# Schematic.net
KiCad netlist of a schematic drawn in EAGLE
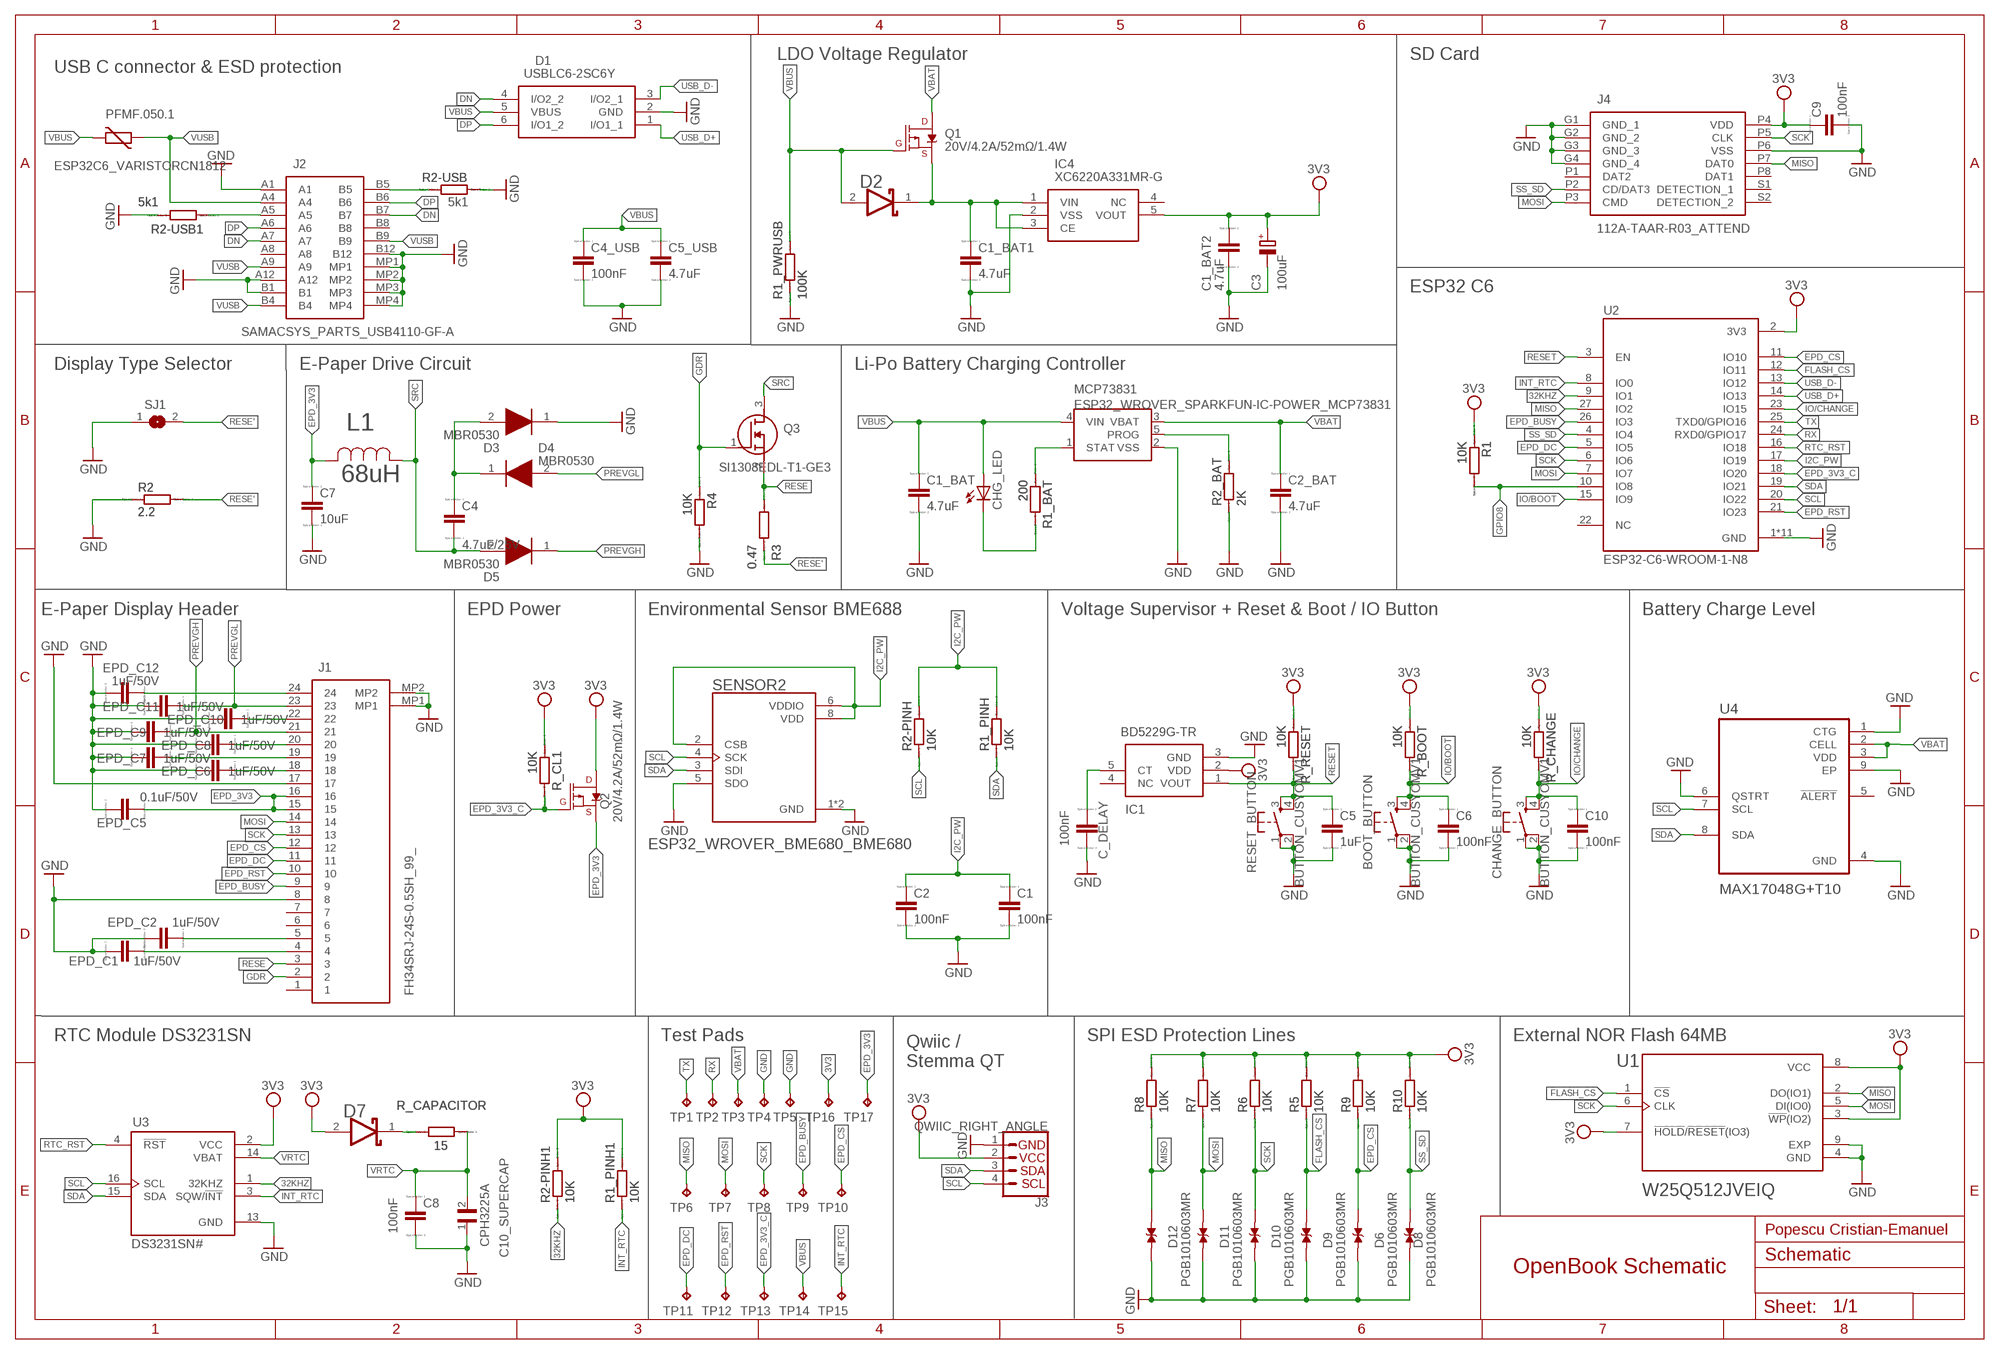
[diagram p0: schematic, sheet 1]

(export (version "E")
  (design (tool "Eeschema 10.0.6"))
  (components
    (comp (ref "BOOT_BUTTON")
      (value "BUTTON_CUSYOMV1")
      (footprint "eagle-import:MYBUTTON")
      (libsource (lib "eagle-import") (part "BUTTON_CUSYOMV1"))
    )
    (comp (ref "C1")
      (value "100nF")
      (footprint "eagle-import:ESP32_WROVER_EAGLE-LTSPICE_C0402")
      (libsource (lib "eagle-import") (part "ESP32_WROVER_EAGLE-LTSPICE_CC0402"))
    )
    (comp (ref "C1_BAT")
      (value "4.7uF")
      (footprint "eagle-import:ESP32_WROVER_EAGLE-LTSPICE_C0402")
      (libsource (lib "eagle-import") (part "ESP32_WROVER_EAGLE-LTSPICE_CC0402-4.7UF"))
    )
    (comp (ref "C1_BAT1")
      (value "4.7uF")
      (footprint "eagle-import:ESP32_WROVER_EAGLE-LTSPICE_C0402")
      (libsource (lib "eagle-import") (part "ESP32_WROVER_EAGLE-LTSPICE_CC0402-4.7UF"))
    )
    (comp (ref "C1_BAT2")
      (value "4.7uF")
      (footprint "eagle-import:ESP32_WROVER_EAGLE-LTSPICE_C0402")
      (libsource (lib "eagle-import") (part "ESP32_WROVER_EAGLE-LTSPICE_CC0402-4.7UF"))
    )
    (comp (ref "C2")
      (value "100nF")
      (footprint "eagle-import:ESP32_WROVER_EAGLE-LTSPICE_C0402")
      (libsource (lib "eagle-import") (part "ESP32_WROVER_EAGLE-LTSPICE_CC0402"))
    )
    (comp (ref "C2_BAT")
      (value "4.7uF")
      (footprint "eagle-import:ESP32_WROVER_EAGLE-LTSPICE_C0402")
      (libsource (lib "eagle-import") (part "ESP32_WROVER_EAGLE-LTSPICE_CC0402-4.7UF"))
    )
    (comp (ref "C3")
      (value "100uF")
      (footprint "eagle-import:RCL_CT3528")
      (libsource (lib "eagle-import") (part "RCL_CPOL-EUCT3528"))
    )
    (comp (ref "C4")
      (value "4.7uF/25V")
      (footprint "eagle-import:ESP32_WROVER_EAGLE-LTSPICE_C0402")
      (libsource (lib "eagle-import") (part "ESP32_WROVER_EAGLE-LTSPICE_CC0402-4.7UF"))
    )
    (comp (ref "C4_USB")
      (value "100nF")
      (footprint "eagle-import:ESP32_WROVER_EAGLE-LTSPICE_C0402")
      (libsource (lib "eagle-import") (part "ESP32_WROVER_EAGLE-LTSPICE_CC0402"))
    )
    (comp (ref "C5")
      (value "1uF")
      (footprint "eagle-import:ESP32_WROVER_EAGLE-LTSPICE_C0402")
      (libsource (lib "eagle-import") (part "ESP32_WROVER_EAGLE-LTSPICE_CC0402"))
    )
    (comp (ref "C5_USB")
      (value "4.7uF")
      (footprint "eagle-import:ESP32_WROVER_EAGLE-LTSPICE_C0402")
      (libsource (lib "eagle-import") (part "ESP32_WROVER_EAGLE-LTSPICE_CC0402-4.7UF"))
    )
    (comp (ref "C6")
      (value "100nF")
      (footprint "eagle-import:ESP32_WROVER_EAGLE-LTSPICE_C0402")
      (libsource (lib "eagle-import") (part "ESP32_WROVER_EAGLE-LTSPICE_CC0402"))
    )
    (comp (ref "C7")
      (value "10uF")
      (footprint "eagle-import:ESP32_WROVER_EAGLE-LTSPICE_C0402")
      (libsource (lib "eagle-import") (part "ESP32_WROVER_EAGLE-LTSPICE_CC0402"))
    )
    (comp (ref "C8")
      (value "100nF")
      (footprint "eagle-import:ESP32_WROVER_EAGLE-LTSPICE_C0402")
      (libsource (lib "eagle-import") (part "ESP32_WROVER_EAGLE-LTSPICE_CC0402"))
    )
    (comp (ref "C9")
      (value "100nF")
      (footprint "eagle-import:ESP32_WROVER_EAGLE-LTSPICE_C0402")
      (libsource (lib "eagle-import") (part "ESP32_WROVER_EAGLE-LTSPICE_CC0402"))
    )
    (comp (ref "C10")
      (value "100nF")
      (footprint "eagle-import:ESP32_WROVER_EAGLE-LTSPICE_C0402")
      (libsource (lib "eagle-import") (part "ESP32_WROVER_EAGLE-LTSPICE_CC0402"))
    )
    (comp (ref "C10_SUPERCAP")
      (value "CPH3225A")
      (footprint "eagle-import:CAPCP3225X100N")
      (fields (field (name "MF") "Seiko Instruments"))
      (libsource (lib "eagle-import") (part "CPH3225A"))
    )
    (comp (ref "CHANGE_BUTTON")
      (value "BUTTON_CUSYOMV1")
      (footprint "eagle-import:MYBUTTON")
      (libsource (lib "eagle-import") (part "BUTTON_CUSYOMV1"))
    )
    (comp (ref "CHG_LED")
      (value "ADAFRUIT_LEDCHIP-LED0603")
      (footprint "eagle-import:ADAFRUIT_CHIP-LED0603")
      (libsource (lib "eagle-import") (part "ADAFRUIT_LEDCHIP-LED0603"))
    )
    (comp (ref "C_DELAY")
      (value "100nF")
      (footprint "eagle-import:ESP32_WROVER_EAGLE-LTSPICE_C0402")
      (libsource (lib "eagle-import") (part "ESP32_WROVER_EAGLE-LTSPICE_CC0402"))
    )
    (comp (ref "D1")
      (value "USBLC6-2SC6Y")
      (footprint "eagle-import:SOT95P280X145-6N")
      (fields (field (name "MF") "STMicroelectronics"))
      (libsource (lib "eagle-import") (part "USBLC6-2SC6Y"))
    )
    (comp (ref "D2")
      (value "ESP32_WROVER_AVX---SD0805S020S1R0_AVX_SD0805S020S1R0_0_0AVX_SD0805S020S1R0_0_0")
      (footprint "eagle-import:ESP32_WROVER_AVX---SD0805S020S1R0_AVX_SD0805S020S1R0_0")
      (fields
        (field (name "DIGIKEY_PART_NUMBER") "478-7800-1-ND")
        (field (name "MF") "AVX")
        (field (name "MOUSER_PART_NUMBER") "581-SD0805S020S1R0")
      )
      (libsource (lib "eagle-import") (part "ESP32_WROVER_AVX---SD0805S020S1R0_AVX_SD0805S020S1R0_0_0AVX_SD0805S020S1R0_0_0"))
    )
    (comp (ref "D3")
      (value "MBR0530")
      (footprint "eagle-import:SOD3716X135N")
      (fields (field (name "MF") "ON Semiconductor"))
      (libsource (lib "eagle-import") (part "MBR0530"))
    )
    (comp (ref "D4")
      (value "MBR0530")
      (footprint "eagle-import:SOD3716X135N")
      (fields (field (name "MF") "ON Semiconductor"))
      (libsource (lib "eagle-import") (part "MBR0530"))
    )
    (comp (ref "D5")
      (value "MBR0530")
      (footprint "eagle-import:SOD3716X135N")
      (fields (field (name "MF") "ON Semiconductor"))
      (libsource (lib "eagle-import") (part "MBR0530"))
    )
    (comp (ref "D6")
      (value "PGB1010603MR")
      (footprint "eagle-import:DIOC1608X36N")
      (fields (field (name "MF") "Littelfuse Inc."))
      (libsource (lib "eagle-import") (part "PGB1010603MR"))
    )
    (comp (ref "D7")
      (value "ESP32_WROVER_AVX---SD0805S020S1R0_AVX_SD0805S020S1R0_0_0AVX_SD0805S020S1R0_0_0")
      (footprint "eagle-import:ESP32_WROVER_AVX---SD0805S020S1R0_AVX_SD0805S020S1R0_0")
      (fields
        (field (name "DIGIKEY_PART_NUMBER") "478-7800-1-ND")
        (field (name "MF") "AVX")
        (field (name "MOUSER_PART_NUMBER") "581-SD0805S020S1R0")
      )
      (libsource (lib "eagle-import") (part "ESP32_WROVER_AVX---SD0805S020S1R0_AVX_SD0805S020S1R0_0_0AVX_SD0805S020S1R0_0_0"))
    )
    (comp (ref "D8")
      (value "PGB1010603MR")
      (footprint "eagle-import:DIOC1608X36N")
      (fields (field (name "MF") "Littelfuse Inc."))
      (libsource (lib "eagle-import") (part "PGB1010603MR"))
    )
    (comp (ref "D9")
      (value "PGB1010603MR")
      (footprint "eagle-import:DIOC1608X36N")
      (fields (field (name "MF") "Littelfuse Inc."))
      (libsource (lib "eagle-import") (part "PGB1010603MR"))
    )
    (comp (ref "D10")
      (value "PGB1010603MR")
      (footprint "eagle-import:DIOC1608X36N")
      (fields (field (name "MF") "Littelfuse Inc."))
      (libsource (lib "eagle-import") (part "PGB1010603MR"))
    )
    (comp (ref "D11")
      (value "PGB1010603MR")
      (footprint "eagle-import:DIOC1608X36N")
      (fields (field (name "MF") "Littelfuse Inc."))
      (libsource (lib "eagle-import") (part "PGB1010603MR"))
    )
    (comp (ref "D12")
      (value "PGB1010603MR")
      (footprint "eagle-import:DIOC1608X36N")
      (fields (field (name "MF") "Littelfuse Inc."))
      (libsource (lib "eagle-import") (part "PGB1010603MR"))
    )
    (comp (ref "EPD_C1")
      (value "1uF/50V")
      (footprint "eagle-import:ESP32_WROVER_EAGLE-LTSPICE_C0402")
      (libsource (lib "eagle-import") (part "ESP32_WROVER_EAGLE-LTSPICE_CC0402-1UF/50V"))
    )
    (comp (ref "EPD_C2")
      (value "1uF/50V")
      (footprint "eagle-import:ESP32_WROVER_EAGLE-LTSPICE_C0402")
      (libsource (lib "eagle-import") (part "ESP32_WROVER_EAGLE-LTSPICE_CC0402-1UF/50V"))
    )
    (comp (ref "EPD_C5")
      (value "0.1uF/50V")
      (footprint "eagle-import:ESP32_WROVER_EAGLE-LTSPICE_C0402")
      (libsource (lib "eagle-import") (part "ESP32_WROVER_EAGLE-LTSPICE_CC0402"))
    )
    (comp (ref "EPD_C6")
      (value "1uF/50V")
      (footprint "eagle-import:ESP32_WROVER_EAGLE-LTSPICE_C0402")
      (libsource (lib "eagle-import") (part "ESP32_WROVER_EAGLE-LTSPICE_CC0402-1UF/50V"))
    )
    (comp (ref "EPD_C7")
      (value "1uF/50V")
      (footprint "eagle-import:ESP32_WROVER_EAGLE-LTSPICE_C0402")
      (libsource (lib "eagle-import") (part "ESP32_WROVER_EAGLE-LTSPICE_CC0402-1UF/50V"))
    )
    (comp (ref "EPD_C8")
      (value "1uF/50V")
      (footprint "eagle-import:ESP32_WROVER_EAGLE-LTSPICE_C0402")
      (libsource (lib "eagle-import") (part "ESP32_WROVER_EAGLE-LTSPICE_CC0402-1UF/50V"))
    )
    (comp (ref "EPD_C9")
      (value "1uF/50V")
      (footprint "eagle-import:ESP32_WROVER_EAGLE-LTSPICE_C0402")
      (libsource (lib "eagle-import") (part "ESP32_WROVER_EAGLE-LTSPICE_CC0402-1UF/50V"))
    )
    (comp (ref "EPD_C10")
      (value "1uF/50V")
      (footprint "eagle-import:ESP32_WROVER_EAGLE-LTSPICE_C0402")
      (libsource (lib "eagle-import") (part "ESP32_WROVER_EAGLE-LTSPICE_CC0402-1UF/50V"))
    )
    (comp (ref "EPD_C11")
      (value "1uF/50V")
      (footprint "eagle-import:ESP32_WROVER_EAGLE-LTSPICE_C0402")
      (libsource (lib "eagle-import") (part "ESP32_WROVER_EAGLE-LTSPICE_CC0402-1UF/50V"))
    )
    (comp (ref "EPD_C12")
      (value "1uF/50V")
      (footprint "eagle-import:ESP32_WROVER_EAGLE-LTSPICE_C0402")
      (libsource (lib "eagle-import") (part "ESP32_WROVER_EAGLE-LTSPICE_CC0402-1UF/50V"))
    )
    (comp (ref "IC1")
      (value "BD5229G-TR")
      (footprint "eagle-import:SOT95P280X125-5N")
      (fields (field (name "MOUSER_PART_NUMBER") "755-BD5229G-TR"))
      (libsource (lib "eagle-import") (part "BD5229G-TR"))
    )
    (comp (ref "IC4")
      (value "XC6220A331MR-G")
      (footprint "eagle-import:SOT95P280X120-5N")
      (fields (field (name "MOUSER_PART_NUMBER") "865-XC6220A331MR-G"))
      (libsource (lib "eagle-import") (part "XC6220A331MR-G"))
    )
    (comp (ref "J1")
      (value "FH34SRJ-24S-0.5SH_99_")
      (footprint "eagle-import:FH34SRJ24S05SH99")
      (fields
        (field (name "MANUFACTURER_PART_NUMBER") "FH34SRJ-24S-0.5SH(99)")
        (field (name "MOUSER_PART_NUMBER") "798-FH34SRJ24S05SH99")
      )
      (libsource (lib "eagle-import") (part "FH34SRJ-24S-0.5SH_99_"))
    )
    (comp (ref "J2")
      (value "SAMACSYS_PARTS_USB4110-GF-A")
      (footprint "eagle-import:SAMACSYS_PARTS_USB4110GFA")
      (fields
        (field (name "MANUFACTURER_PART_NUMBER") "USB4110-GF-A")
        (field (name "MOUSER_PART_NUMBER") "640-USB4110-GF-A")
      )
      (libsource (lib "eagle-import") (part "SAMACSYS_PARTS_USB4110-GF-A"))
    )
    (comp (ref "J3")
      (value "QWIIC_RIGHT_ANGLE")
      (footprint "eagle-import:JST04_1MM_RA")
      (libsource (lib "eagle-import") (part "QWIIC_CONNECTORJS-1MM"))
    )
    (comp (ref "J4")
      (value "112A-TAAR-R03_ATTEND")
      (footprint "eagle-import:112ATAARR03ATTEND")
      (fields (field (name "MANUFACTURER_PART_NUMBER") "112A-TAAR-R03 ATTEND"))
      (libsource (lib "eagle-import") (part "112A-TAAR-R03_ATTEND"))
    )
    (comp (ref "L1")
      (value "68uH")
      (footprint "eagle-import:IND_4828-WE-TPC_WRE")
      (fields
        (field (name "MANUFACTURER_PART_NUMBER") "744043680")
        (field (name "COPYRIGHT") "Copyright (C) 2024 Ultra Librarian. All rights reserved.")
      )
      (libsource (lib "eagle-import") (part "744043680IND_4828-WE-TPC_WRE"))
    )
    (comp (ref "MCP73831")
      (value "ESP32_WROVER_SPARKFUN-IC-POWER_MCP73831")
      (footprint "eagle-import:ESP32_WROVER_SPARKFUN-IC-POWER_SOT23-5")
      (libsource (lib "eagle-import") (part "ESP32_WROVER_SPARKFUN-IC-POWER_MCP73831"))
    )
    (comp (ref "PFMF.050.1")
      (value "ESP32C6_VARISTORCN1812")
      (footprint "eagle-import:ESP32C6_VARISTOR_CT_CN1812")
      (libsource (lib "eagle-import") (part "ESP32C6_VARISTORCN1812"))
    )
    (comp (ref "Q1")
      (value "20V/4.2A/52mΩ/1.4W")
      (footprint "eagle-import:ESP32_WROVER_SPARKFUN-DISCRETESEMI_SOT23-3")
      (libsource (lib "eagle-import") (part "ESP32_WROVER_SPARKFUN-DISCRETESEMI_MOSFET_PCH-DMG2305UX-7"))
    )
    (comp (ref "Q2")
      (value "20V/4.2A/52mΩ/1.4W")
      (footprint "eagle-import:ESP32_WROVER_SPARKFUN-DISCRETESEMI_SOT23-3")
      (libsource (lib "eagle-import") (part "ESP32_WROVER_SPARKFUN-DISCRETESEMI_MOSFET_PCH-DMG2305UX-7"))
    )
    (comp (ref "Q3")
      (value "SI1308EDL-T1-GE3")
      (footprint "eagle-import:SOT65P210X110-3N")
      (fields (field (name "MF") "Vishay Siliconix"))
      (libsource (lib "eagle-import") (part "SI1308EDL-T1-GE3"))
    )
    (comp (ref "R1")
      (value "10K")
      (footprint "eagle-import:ESP32_WROVER_EAGLE-LTSPICE_R0402")
      (libsource (lib "eagle-import") (part "ESP32_WROVER_EAGLE-LTSPICE_RR0402"))
    )
    (comp (ref "R1_BAT")
      (value "200")
      (footprint "eagle-import:ESP32_WROVER_EAGLE-LTSPICE_R0402")
      (libsource (lib "eagle-import") (part "ESP32_WROVER_EAGLE-LTSPICE_RR0402-200"))
    )
    (comp (ref "R1_PINH")
      (value "10K")
      (footprint "eagle-import:ESP32_WROVER_EAGLE-LTSPICE_R0402")
      (libsource (lib "eagle-import") (part "ESP32_WROVER_EAGLE-LTSPICE_RR0402"))
    )
    (comp (ref "R1_PINH1")
      (value "10K")
      (footprint "eagle-import:ESP32_WROVER_EAGLE-LTSPICE_R0402")
      (libsource (lib "eagle-import") (part "ESP32_WROVER_EAGLE-LTSPICE_RR0402"))
    )
    (comp (ref "R1_PWRUSB")
      (value "100K")
      (footprint "eagle-import:ESP32_WROVER_EAGLE-LTSPICE_R0402")
      (libsource (lib "eagle-import") (part "ESP32_WROVER_EAGLE-LTSPICE_RR0402-MCS-100K"))
    )
    (comp (ref "R2")
      (value "2.2")
      (footprint "eagle-import:ESP32_WROVER_EAGLE-LTSPICE_R0402")
      (libsource (lib "eagle-import") (part "ESP32_WROVER_EAGLE-LTSPICE_RR0402"))
    )
    (comp (ref "R2-PINH")
      (value "10K")
      (footprint "eagle-import:ESP32_WROVER_EAGLE-LTSPICE_R0402")
      (libsource (lib "eagle-import") (part "ESP32_WROVER_EAGLE-LTSPICE_RR0402"))
    )
    (comp (ref "R2-PINH1")
      (value "10K")
      (footprint "eagle-import:ESP32_WROVER_EAGLE-LTSPICE_R0402")
      (libsource (lib "eagle-import") (part "ESP32_WROVER_EAGLE-LTSPICE_RR0402"))
    )
    (comp (ref "R2-USB")
      (value "5k1")
      (footprint "eagle-import:ESP32_WROVER_EAGLE-LTSPICE_R0402")
      (libsource (lib "eagle-import") (part "ESP32_WROVER_EAGLE-LTSPICE_RR0402-MCS"))
    )
    (comp (ref "R2-USB1")
      (value "5k1")
      (footprint "eagle-import:ESP32_WROVER_EAGLE-LTSPICE_R0402")
      (libsource (lib "eagle-import") (part "ESP32_WROVER_EAGLE-LTSPICE_RR0402-MCS"))
    )
    (comp (ref "R2_BAT")
      (value "2K")
      (footprint "eagle-import:ESP32_WROVER_EAGLE-LTSPICE_R0402")
      (libsource (lib "eagle-import") (part "ESP32_WROVER_EAGLE-LTSPICE_RR0402"))
    )
    (comp (ref "R3")
      (value "0.47")
      (footprint "eagle-import:ESP32_WROVER_EAGLE-LTSPICE_R0402")
      (libsource (lib "eagle-import") (part "ESP32_WROVER_EAGLE-LTSPICE_RR0402"))
    )
    (comp (ref "R4")
      (value "10K")
      (footprint "eagle-import:ESP32_WROVER_EAGLE-LTSPICE_R0402")
      (libsource (lib "eagle-import") (part "ESP32_WROVER_EAGLE-LTSPICE_RR0402"))
    )
    (comp (ref "R5")
      (value "10K")
      (footprint "eagle-import:ESP32_WROVER_EAGLE-LTSPICE_R0402")
      (libsource (lib "eagle-import") (part "ESP32_WROVER_EAGLE-LTSPICE_RR0402"))
    )
    (comp (ref "R6")
      (value "10K")
      (footprint "eagle-import:ESP32_WROVER_EAGLE-LTSPICE_R0402")
      (libsource (lib "eagle-import") (part "ESP32_WROVER_EAGLE-LTSPICE_RR0402"))
    )
    (comp (ref "R7")
      (value "10K")
      (footprint "eagle-import:ESP32_WROVER_EAGLE-LTSPICE_R0402")
      (libsource (lib "eagle-import") (part "ESP32_WROVER_EAGLE-LTSPICE_RR0402"))
    )
    (comp (ref "R8")
      (value "10K")
      (footprint "eagle-import:ESP32_WROVER_EAGLE-LTSPICE_R0402")
      (libsource (lib "eagle-import") (part "ESP32_WROVER_EAGLE-LTSPICE_RR0402"))
    )
    (comp (ref "R9")
      (value "10K")
      (footprint "eagle-import:ESP32_WROVER_EAGLE-LTSPICE_R0402")
      (libsource (lib "eagle-import") (part "ESP32_WROVER_EAGLE-LTSPICE_RR0402"))
    )
    (comp (ref "R10")
      (value "10K")
      (footprint "eagle-import:ESP32_WROVER_EAGLE-LTSPICE_R0402")
      (libsource (lib "eagle-import") (part "ESP32_WROVER_EAGLE-LTSPICE_RR0402"))
    )
    (comp (ref "RESET_BUTTON")
      (value "BUTTON_CUSYOMV1")
      (footprint "eagle-import:MYBUTTON")
      (libsource (lib "eagle-import") (part "BUTTON_CUSYOMV1"))
    )
    (comp (ref "R_BOOT")
      (value "10K")
      (footprint "eagle-import:ESP32_WROVER_EAGLE-LTSPICE_R0402")
      (libsource (lib "eagle-import") (part "ESP32_WROVER_EAGLE-LTSPICE_RR0402"))
    )
    (comp (ref "R_CAPACITOR")
      (value "15")
      (footprint "eagle-import:ESP32_WROVER_EAGLE-LTSPICE_R0402")
      (libsource (lib "eagle-import") (part "ESP32_WROVER_EAGLE-LTSPICE_RR0402"))
    )
    (comp (ref "R_CHANGE")
      (value "10K")
      (footprint "eagle-import:ESP32_WROVER_EAGLE-LTSPICE_R0402")
      (libsource (lib "eagle-import") (part "ESP32_WROVER_EAGLE-LTSPICE_RR0402"))
    )
    (comp (ref "R_CL1")
      (value "10K")
      (footprint "eagle-import:ESP32_WROVER_EAGLE-LTSPICE_R0402")
      (libsource (lib "eagle-import") (part "ESP32_WROVER_EAGLE-LTSPICE_RR0402"))
    )
    (comp (ref "R_RESET")
      (value "10K")
      (footprint "eagle-import:ESP32_WROVER_EAGLE-LTSPICE_R0402")
      (libsource (lib "eagle-import") (part "ESP32_WROVER_EAGLE-LTSPICE_RR0402"))
    )
    (comp (ref "SENSOR2")
      (value "ESP32_WROVER_BME680_BME680")
      (footprint "eagle-import:ESP32_WROVER_BME680_PSON80P300X300X100-8N")
      (fields (field (name "MF") "Bosch Sensortec") (field (name "MP") "BME680"))
      (libsource (lib "eagle-import") (part "ESP32_WROVER_BME680_BME680"))
    )
    (comp (ref "SJ1") (value "SJ") (footprint "eagle-import:SJ") (libsource (lib "eagle-import") (part "SJ")))
    (comp (ref "TP1")
      (value "TPTP20R")
      (footprint "eagle-import:TP20R")
      (libsource (lib "eagle-import") (part "TPTP20R"))
    )
    (comp (ref "TP2")
      (value "TPTP20R")
      (footprint "eagle-import:TP20R")
      (libsource (lib "eagle-import") (part "TPTP20R"))
    )
    (comp (ref "TP3")
      (value "TPTP20R")
      (footprint "eagle-import:TP20R")
      (libsource (lib "eagle-import") (part "TPTP20R"))
    )
    (comp (ref "TP4")
      (value "TPTP20R")
      (footprint "eagle-import:TP20R")
      (libsource (lib "eagle-import") (part "TPTP20R"))
    )
    (comp (ref "TP5")
      (value "TPTP20R")
      (footprint "eagle-import:TP20R")
      (libsource (lib "eagle-import") (part "TPTP20R"))
    )
    (comp (ref "TP6")
      (value "TPTP20R")
      (footprint "eagle-import:TP20R")
      (libsource (lib "eagle-import") (part "TPTP20R"))
    )
    (comp (ref "TP7")
      (value "TPTP20R")
      (footprint "eagle-import:TP20R")
      (libsource (lib "eagle-import") (part "TPTP20R"))
    )
    (comp (ref "TP8")
      (value "TPTP20R")
      (footprint "eagle-import:TP20R")
      (libsource (lib "eagle-import") (part "TPTP20R"))
    )
    (comp (ref "TP9")
      (value "TPTP20R")
      (footprint "eagle-import:TP20R")
      (libsource (lib "eagle-import") (part "TPTP20R"))
    )
    (comp (ref "TP10")
      (value "TPTP20R")
      (footprint "eagle-import:TP20R")
      (libsource (lib "eagle-import") (part "TPTP20R"))
    )
    (comp (ref "TP11")
      (value "TPTP20R")
      (footprint "eagle-import:TP20R")
      (libsource (lib "eagle-import") (part "TPTP20R"))
    )
    (comp (ref "TP12")
      (value "TPTP20R")
      (footprint "eagle-import:TP20R")
      (libsource (lib "eagle-import") (part "TPTP20R"))
    )
    (comp (ref "TP13")
      (value "TPTP20R")
      (footprint "eagle-import:TP20R")
      (libsource (lib "eagle-import") (part "TPTP20R"))
    )
    (comp (ref "TP14")
      (value "TPTP20R")
      (footprint "eagle-import:TP20R")
      (libsource (lib "eagle-import") (part "TPTP20R"))
    )
    (comp (ref "TP15")
      (value "TPTP20R")
      (footprint "eagle-import:TP20R")
      (libsource (lib "eagle-import") (part "TPTP20R"))
    )
    (comp (ref "TP16")
      (value "TPTP20R")
      (footprint "eagle-import:TP20R")
      (libsource (lib "eagle-import") (part "TPTP20R"))
    )
    (comp (ref "TP17")
      (value "TPTP20R")
      (footprint "eagle-import:TP20R")
      (libsource (lib "eagle-import") (part "TPTP20R"))
    )
    (comp (ref "U1")
      (value "W25Q512JVEIQ")
      (footprint "eagle-import:SON127P600X800X80-9N")
      (fields (field (name "MF") "Winbond Electronics"))
      (libsource (lib "eagle-import") (part "W25Q512JVEIQ"))
    )
    (comp (ref "U2")
      (value "ESP32-C6-WROOM-1-N8")
      (footprint "eagle-import:XCVR_ESP32-C6-WROOM-1-N8")
      (fields (field (name "MF") "Espressif Systems"))
      (libsource (lib "eagle-import") (part "ESP32-C6-WROOM-1-N8"))
    )
    (comp (ref "U3")
      (value "DS3231SN#")
      (footprint "eagle-import:SOIC127P1032X265-16N")
      (fields (field (name "MF") "Analog Devices"))
      (libsource (lib "eagle-import") (part "DS3231SN#"))
    )
    (comp (ref "U4")
      (value "MAX17048G+T10")
      (footprint "eagle-import:SON50P200X200X80-9N")
      (fields (field (name "MF") "Analog Devices"))
      (libsource (lib "eagle-import") (part "MAX17048G+T10"))
    )
  )
  (nets
    (net (code "1") (name "3V3") (class "Default")
      (node (ref "C1_BAT2") (pin "1") (pinfunction "1_1") (pintype "passive"))
      (node (ref "C3") (pin "+") (pinfunction "+_+") (pintype "passive"))
      (node (ref "C9") (pin "1") (pinfunction "1_1") (pintype "passive"))
      (node (ref "D7") (pin "2") (pinfunction "ANODE_2") (pintype "bidirectional"))
      (node (ref "IC1") (pin "2") (pinfunction "VDD_2") (pintype "bidirectional"))
      (node (ref "IC4") (pin "5") (pinfunction "VOUT_5") (pintype "bidirectional"))
      (node (ref "J3") (pin "2") (pinfunction "2_2") (pintype "power_in"))
      (node (ref "J4") (pin "P4") (pinfunction "VDD_P4") (pintype "bidirectional"))
      (node (ref "Q2") (pin "3") (pinfunction "D_3") (pintype "bidirectional"))
      (node (ref "R1") (pin "1") (pinfunction "1_1") (pintype "passive"))
      (node (ref "R10") (pin "2") (pinfunction "2_2") (pintype "passive"))
      (node (ref "R1_PINH1") (pin "2") (pinfunction "2_2") (pintype "passive"))
      (node (ref "R2-PINH1") (pin "2") (pinfunction "2_2") (pintype "passive"))
      (node (ref "R5") (pin "2") (pinfunction "2_2") (pintype "passive"))
      (node (ref "R6") (pin "2") (pinfunction "2_2") (pintype "passive"))
      (node (ref "R7") (pin "2") (pinfunction "2_2") (pintype "passive"))
      (node (ref "R8") (pin "2") (pinfunction "2_2") (pintype "passive"))
      (node (ref "R9") (pin "2") (pinfunction "2_2") (pintype "passive"))
      (node (ref "R_BOOT") (pin "1") (pinfunction "1_1") (pintype "passive"))
      (node (ref "R_CHANGE") (pin "1") (pinfunction "1_1") (pintype "passive"))
      (node (ref "R_CL1") (pin "1") (pinfunction "1_1") (pintype "passive"))
      (node (ref "R_RESET") (pin "1") (pinfunction "1_1") (pintype "passive"))
      (node (ref "TP16") (pin "TP") (pinfunction "TP_TP") (pintype "input"))
      (node (ref "U1") (pin "3") (pinfunction "~{WP}(IO2)_3") (pintype "bidirectional"))
      (node (ref "U1") (pin "7") (pinfunction "~{HOLD}/~{RESET}(IO3)_7") (pintype "bidirectional"))
      (node (ref "U1") (pin "8") (pinfunction "VCC_8") (pintype "power_in"))
      (node (ref "U2") (pin "2") (pinfunction "3V3_2") (pintype "power_in"))
      (node (ref "U3") (pin "2") (pinfunction "VCC_2") (pintype "power_in"))
    )
    (net (code "2") (name "32KHZ") (class "Default")
      (node (ref "R2-PINH1") (pin "1") (pinfunction "1_1") (pintype "passive"))
      (node (ref "U2") (pin "9") (pinfunction "IO1_9") (pintype "bidirectional"))
      (node (ref "U3") (pin "1") (pinfunction "32KHZ_1") (pintype "output"))
    )
    (net (code "3") (name "DN") (class "Default")
      (node (ref "D1") (pin "4") (pinfunction "I/O2_2_4") (pintype "bidirectional"))
      (node (ref "J2") (pin "A7") (pinfunction "A7_A7") (pintype "bidirectional"))
      (node (ref "J2") (pin "B7") (pinfunction "B7_B7") (pintype "bidirectional"))
    )
    (net (code "4") (name "DP") (class "Default")
      (node (ref "D1") (pin "6") (pinfunction "I/O1_2_6") (pintype "bidirectional"))
      (node (ref "J2") (pin "A6") (pinfunction "A6_A6") (pintype "bidirectional"))
      (node (ref "J2") (pin "B6") (pinfunction "B6_B6") (pintype "bidirectional"))
    )
    (net (code "5") (name "EPD_3V3") (class "Default")
      (node (ref "C7") (pin "1") (pinfunction "1_1") (pintype "passive"))
      (node (ref "EPD_C5") (pin "1") (pinfunction "1_1") (pintype "passive"))
      (node (ref "J1") (pin "15") (pinfunction "15_15") (pintype "bidirectional"))
      (node (ref "J1") (pin "16") (pinfunction "16_16") (pintype "bidirectional"))
      (node (ref "L1") (pin "2") (pinfunction "2_2") (pintype "passive"))
      (node (ref "Q2") (pin "2") (pinfunction "S_2") (pintype "bidirectional"))
      (node (ref "TP17") (pin "TP") (pinfunction "TP_TP") (pintype "input"))
    )
    (net (code "6") (name "EPD_3V3_C") (class "Default")
      (node (ref "Q2") (pin "1") (pinfunction "G_1") (pintype "bidirectional"))
      (node (ref "R_CL1") (pin "2") (pinfunction "2_2") (pintype "passive"))
      (node (ref "TP13") (pin "TP") (pinfunction "TP_TP") (pintype "input"))
      (node (ref "U2") (pin "18") (pinfunction "IO20_18") (pintype "bidirectional"))
    )
    (net (code "7") (name "EPD_BUSY") (class "Default")
      (node (ref "J1") (pin "9") (pinfunction "9_9") (pintype "bidirectional"))
      (node (ref "TP9") (pin "TP") (pinfunction "TP_TP") (pintype "input"))
      (node (ref "U2") (pin "26") (pinfunction "IO3_26") (pintype "bidirectional"))
    )
    (net (code "8") (name "EPD_CS") (class "Default")
      (node (ref "D6") (pin "2") (pinfunction "2_2") (pintype "passive"))
      (node (ref "J1") (pin "12") (pinfunction "12_12") (pintype "bidirectional"))
      (node (ref "R9") (pin "1") (pinfunction "1_1") (pintype "passive"))
      (node (ref "TP10") (pin "TP") (pinfunction "TP_TP") (pintype "input"))
      (node (ref "U2") (pin "11") (pinfunction "IO10_11") (pintype "bidirectional"))
    )
    (net (code "9") (name "EPD_DC") (class "Default")
      (node (ref "J1") (pin "11") (pinfunction "11_11") (pintype "bidirectional"))
      (node (ref "TP11") (pin "TP") (pinfunction "TP_TP") (pintype "input"))
      (node (ref "U2") (pin "5") (pinfunction "IO5_5") (pintype "bidirectional"))
    )
    (net (code "10") (name "EPD_RST") (class "Default")
      (node (ref "J1") (pin "10") (pinfunction "10_10") (pintype "bidirectional"))
      (node (ref "TP12") (pin "TP") (pinfunction "TP_TP") (pintype "input"))
      (node (ref "U2") (pin "21") (pinfunction "IO23_21") (pintype "bidirectional"))
    )
    (net (code "11") (name "FLASH_CS") (class "Default")
      (node (ref "D9") (pin "2") (pinfunction "2_2") (pintype "passive"))
      (node (ref "R5") (pin "1") (pinfunction "1_1") (pintype "passive"))
      (node (ref "U1") (pin "1") (pinfunction "~{CS}_1") (pintype "input"))
      (node (ref "U2") (pin "12") (pinfunction "IO11_12") (pintype "bidirectional"))
    )
    (net (code "12") (name "GDR") (class "Default")
      (node (ref "J1") (pin "2") (pinfunction "2_2") (pintype "bidirectional"))
      (node (ref "Q3") (pin "1") (pinfunction "G_1") (pintype "bidirectional"))
      (node (ref "R4") (pin "1") (pinfunction "1_1") (pintype "passive"))
    )
    (net (code "13") (name "GND") (class "Default")
      (node (ref "BOOT_BUTTON") (pin "1") (pinfunction "1_1") (pintype "passive"))
      (node (ref "BOOT_BUTTON") (pin "2") (pinfunction "2_2") (pintype "passive"))
      (node (ref "C1") (pin "2") (pinfunction "2_2") (pintype "passive"))
      (node (ref "C10") (pin "2") (pinfunction "2_2") (pintype "passive"))
      (node (ref "C10_SUPERCAP") (pin "1") (pinfunction "1_1") (pintype "passive"))
      (node (ref "C1_BAT") (pin "2") (pinfunction "2_2") (pintype "passive"))
      (node (ref "C1_BAT1") (pin "2") (pinfunction "2_2") (pintype "passive"))
      (node (ref "C1_BAT2") (pin "2") (pinfunction "2_2") (pintype "passive"))
      (node (ref "C2") (pin "2") (pinfunction "2_2") (pintype "passive"))
      (node (ref "C2_BAT") (pin "2") (pinfunction "2_2") (pintype "passive"))
      (node (ref "C3") (pin "-") (pinfunction "-_-") (pintype "passive"))
      (node (ref "C4_USB") (pin "2") (pinfunction "2_2") (pintype "passive"))
      (node (ref "C5") (pin "2") (pinfunction "2_2") (pintype "passive"))
      (node (ref "C5_USB") (pin "2") (pinfunction "2_2") (pintype "passive"))
      (node (ref "C6") (pin "2") (pinfunction "2_2") (pintype "passive"))
      (node (ref "C7") (pin "2") (pinfunction "2_2") (pintype "passive"))
      (node (ref "C8") (pin "2") (pinfunction "2_2") (pintype "passive"))
      (node (ref "C9") (pin "2") (pinfunction "2_2") (pintype "passive"))
      (node (ref "CHANGE_BUTTON") (pin "1") (pinfunction "1_1") (pintype "passive"))
      (node (ref "CHANGE_BUTTON") (pin "2") (pinfunction "2_2") (pintype "passive"))
      (node (ref "C_DELAY") (pin "2") (pinfunction "2_2") (pintype "passive"))
      (node (ref "D1") (pin "2") (pinfunction "GND_2") (pintype "bidirectional"))
      (node (ref "D10") (pin "1") (pinfunction "1_1") (pintype "passive"))
      (node (ref "D11") (pin "1") (pinfunction "1_1") (pintype "passive"))
      (node (ref "D12") (pin "1") (pinfunction "1_1") (pintype "passive"))
      (node (ref "D3") (pin "1") (pinfunction "K_1") (pintype "bidirectional"))
      (node (ref "D6") (pin "1") (pinfunction "1_1") (pintype "passive"))
      (node (ref "D8") (pin "1") (pinfunction "1_1") (pintype "passive"))
      (node (ref "D9") (pin "1") (pinfunction "1_1") (pintype "passive"))
      (node (ref "EPD_C1") (pin "2") (pinfunction "2_2") (pintype "passive"))
      (node (ref "EPD_C10") (pin "2") (pinfunction "2_2") (pintype "passive"))
      (node (ref "EPD_C11") (pin "2") (pinfunction "2_2") (pintype "passive"))
      (node (ref "EPD_C12") (pin "2") (pinfunction "2_2") (pintype "passive"))
      (node (ref "EPD_C2") (pin "2") (pinfunction "2_2") (pintype "passive"))
      (node (ref "EPD_C5") (pin "2") (pinfunction "2_2") (pintype "passive"))
      (node (ref "EPD_C6") (pin "2") (pinfunction "2_2") (pintype "passive"))
      (node (ref "EPD_C7") (pin "2") (pinfunction "2_2") (pintype "passive"))
      (node (ref "EPD_C8") (pin "2") (pinfunction "2_2") (pintype "passive"))
      (node (ref "EPD_C9") (pin "2") (pinfunction "2_2") (pintype "passive"))
      (node (ref "IC1") (pin "3") (pinfunction "GND_3") (pintype "bidirectional"))
      (node (ref "IC4") (pin "2") (pinfunction "VSS_2") (pintype "bidirectional"))
      (node (ref "J1") (pin "17") (pinfunction "17_17") (pintype "bidirectional"))
      (node (ref "J1") (pin "8") (pinfunction "8_8") (pintype "bidirectional"))
      (node (ref "J1") (pin "MP1") (pinfunction "MP1_MP1") (pintype "bidirectional"))
      (node (ref "J1") (pin "MP2") (pinfunction "MP2_MP2") (pintype "bidirectional"))
      (node (ref "J2") (pin "A1") (pinfunction "A1_A1") (pintype "bidirectional"))
      (node (ref "J2") (pin "A12") (pinfunction "A12_A12") (pintype "bidirectional"))
      (node (ref "J2") (pin "B1") (pinfunction "B1_B1") (pintype "bidirectional"))
      (node (ref "J2") (pin "B12") (pinfunction "B12_B12") (pintype "bidirectional"))
      (node (ref "J2") (pin "MP1") (pinfunction "MP1_MP1") (pintype "bidirectional"))
      (node (ref "J2") (pin "MP2") (pinfunction "MP2_MP2") (pintype "bidirectional"))
      (node (ref "J2") (pin "MP3") (pinfunction "MP3_MP3") (pintype "bidirectional"))
      (node (ref "J2") (pin "MP4") (pinfunction "MP4_MP4") (pintype "bidirectional"))
      (node (ref "J3") (pin "1") (pinfunction "1_1") (pintype "power_in"))
      (node (ref "J4") (pin "G1") (pinfunction "GND_1_G1") (pintype "bidirectional"))
      (node (ref "J4") (pin "G2") (pinfunction "GND_2_G2") (pintype "bidirectional"))
      (node (ref "J4") (pin "G3") (pinfunction "GND_3_G3") (pintype "bidirectional"))
      (node (ref "J4") (pin "G4") (pinfunction "GND_4_G4") (pintype "bidirectional"))
      (node (ref "J4") (pin "P6") (pinfunction "VSS_P6") (pintype "bidirectional"))
      (node (ref "MCP73831") (pin "2") (pinfunction "VSS_2") (pintype "power_in"))
      (node (ref "R1_PWRUSB") (pin "1") (pinfunction "1_1") (pintype "passive"))
      (node (ref "R2") (pin "1") (pinfunction "1_1") (pintype "passive"))
      (node (ref "R2-USB") (pin "2") (pinfunction "2_2") (pintype "passive"))
      (node (ref "R2-USB1") (pin "1") (pinfunction "1_1") (pintype "passive"))
      (node (ref "R2_BAT") (pin "1") (pinfunction "1_1") (pintype "passive"))
      (node (ref "R4") (pin "2") (pinfunction "2_2") (pintype "passive"))
      (node (ref "RESET_BUTTON") (pin "1") (pinfunction "1_1") (pintype "passive"))
      (node (ref "RESET_BUTTON") (pin "2") (pinfunction "2_2") (pintype "passive"))
      (node (ref "SENSOR2") (pin "1") (pinfunction "GND_1") (pintype "power_in"))
      (node (ref "SENSOR2") (pin "5") (pinfunction "SDO_5") (pintype "bidirectional"))
      (node (ref "SENSOR2") (pin "7") (pinfunction "GND_7") (pintype "power_in"))
      (node (ref "SJ1") (pin "1") (pinfunction "1_1") (pintype "passive"))
      (node (ref "TP4") (pin "TP") (pinfunction "TP_TP") (pintype "input"))
      (node (ref "TP5") (pin "TP") (pinfunction "TP_TP") (pintype "input"))
      (node (ref "U1") (pin "4") (pinfunction "GND_4") (pintype "power_in"))
      (node (ref "U1") (pin "9") (pinfunction "EXP_9") (pintype "passive"))
      (node (ref "U2") (pin "1") (pinfunction "GND_1") (pintype "power_in"))
      (node (ref "U2") (pin "28") (pinfunction "GND_28") (pintype "power_in"))
      (node (ref "U2") (pin "29_1") (pinfunction "GND_29_1") (pintype "power_in"))
      (node (ref "U2") (pin "29_2") (pinfunction "GND_29_2") (pintype "power_in"))
      (node (ref "U2") (pin "29_3") (pinfunction "GND_29_3") (pintype "power_in"))
      (node (ref "U2") (pin "29_4") (pinfunction "GND_29_4") (pintype "power_in"))
      (node (ref "U2") (pin "29_5") (pinfunction "GND_29_5") (pintype "power_in"))
      (node (ref "U2") (pin "29_6") (pinfunction "GND_29_6") (pintype "power_in"))
      (node (ref "U2") (pin "29_7") (pinfunction "GND_29_7") (pintype "power_in"))
      (node (ref "U2") (pin "29_8") (pinfunction "GND_29_8") (pintype "power_in"))
      (node (ref "U2") (pin "29_9") (pinfunction "GND_29_9") (pintype "power_in"))
      (node (ref "U3") (pin "13") (pinfunction "GND_13") (pintype "power_in"))
      (node (ref "U4") (pin "1") (pinfunction "CTG_1") (pintype "power_in"))
      (node (ref "U4") (pin "4") (pinfunction "GND_4") (pintype "power_in"))
      (node (ref "U4") (pin "6") (pinfunction "QSTRT_6") (pintype "input"))
      (node (ref "U4") (pin "9") (pinfunction "EP_9") (pintype "power_in"))
    )
    (net (code "14") (name "GPIO8") (class "Default")
      (node (ref "R1") (pin "2") (pinfunction "2_2") (pintype "passive"))
      (node (ref "U2") (pin "10") (pinfunction "IO8_10") (pintype "bidirectional"))
    )
    (net (code "15") (name "I2C_PW") (class "Default")
      (node (ref "C1") (pin "1") (pinfunction "1_1") (pintype "passive"))
      (node (ref "C2") (pin "1") (pinfunction "1_1") (pintype "passive"))
      (node (ref "R1_PINH") (pin "2") (pinfunction "2_2") (pintype "passive"))
      (node (ref "R2-PINH") (pin "2") (pinfunction "2_2") (pintype "passive"))
      (node (ref "SENSOR2") (pin "2") (pinfunction "CSB_2") (pintype "input"))
      (node (ref "SENSOR2") (pin "6") (pinfunction "VDDIO_6") (pintype "power_in"))
      (node (ref "SENSOR2") (pin "8") (pinfunction "VDD_8") (pintype "power_in"))
      (node (ref "U2") (pin "17") (pinfunction "IO19_17") (pintype "bidirectional"))
    )
    (net (code "16") (name "INT_RTC") (class "Default")
      (node (ref "R1_PINH1") (pin "1") (pinfunction "1_1") (pintype "passive"))
      (node (ref "TP15") (pin "TP") (pinfunction "TP_TP") (pintype "input"))
      (node (ref "U2") (pin "8") (pinfunction "IO0_8") (pintype "bidirectional"))
      (node (ref "U3") (pin "3") (pinfunction "SQW/~{INT}_3") (pintype "output"))
    )
    (net (code "17") (name "IO{slash}BOOT") (class "Default")
      (node (ref "BOOT_BUTTON") (pin "3") (pinfunction "3_3") (pintype "passive"))
      (node (ref "BOOT_BUTTON") (pin "4") (pinfunction "4_4") (pintype "passive"))
      (node (ref "C6") (pin "1") (pinfunction "1_1") (pintype "passive"))
      (node (ref "R_BOOT") (pin "2") (pinfunction "2_2") (pintype "passive"))
      (node (ref "U2") (pin "15") (pinfunction "IO9_15") (pintype "bidirectional"))
    )
    (net (code "18") (name "IO{slash}CHANGE") (class "Default")
      (node (ref "C10") (pin "1") (pinfunction "1_1") (pintype "passive"))
      (node (ref "CHANGE_BUTTON") (pin "3") (pinfunction "3_3") (pintype "passive"))
      (node (ref "CHANGE_BUTTON") (pin "4") (pinfunction "4_4") (pintype "passive"))
      (node (ref "R_CHANGE") (pin "2") (pinfunction "2_2") (pintype "passive"))
      (node (ref "U2") (pin "23") (pinfunction "IO15_23") (pintype "bidirectional"))
    )
    (net (code "19") (name "MISO") (class "Default")
      (node (ref "D12") (pin "2") (pinfunction "2_2") (pintype "passive"))
      (node (ref "J4") (pin "P7") (pinfunction "DAT0_P7") (pintype "bidirectional"))
      (node (ref "R8") (pin "1") (pinfunction "1_1") (pintype "passive"))
      (node (ref "TP6") (pin "TP") (pinfunction "TP_TP") (pintype "input"))
      (node (ref "U1") (pin "2") (pinfunction "DO(IO1)_2") (pintype "bidirectional"))
      (node (ref "U2") (pin "27") (pinfunction "IO2_27") (pintype "bidirectional"))
    )
    (net (code "20") (name "MOSI") (class "Default")
      (node (ref "D11") (pin "2") (pinfunction "2_2") (pintype "passive"))
      (node (ref "J1") (pin "14") (pinfunction "14_14") (pintype "bidirectional"))
      (node (ref "J4") (pin "P3") (pinfunction "CMD_P3") (pintype "bidirectional"))
      (node (ref "R7") (pin "1") (pinfunction "1_1") (pintype "passive"))
      (node (ref "TP7") (pin "TP") (pinfunction "TP_TP") (pintype "input"))
      (node (ref "U1") (pin "5") (pinfunction "DI(IO0)_5") (pintype "bidirectional"))
      (node (ref "U2") (pin "7") (pinfunction "IO7_7") (pintype "bidirectional"))
    )
    (net (code "21") (name "Net-(CHG_LED-PadC)") (class "Default")
      (node (ref "CHG_LED") (pin "C") (pinfunction "C_C") (pintype "passive"))
      (node (ref "R1_BAT") (pin "2") (pinfunction "2_2") (pintype "passive"))
    )
    (net (code "22") (name "Net-(D2-CATHODE)") (class "Default")
      (node (ref "C1_BAT1") (pin "1") (pinfunction "1_1") (pintype "passive"))
      (node (ref "D2") (pin "1") (pinfunction "CATHODE_1") (pintype "bidirectional"))
      (node (ref "IC4") (pin "1") (pinfunction "VIN_1") (pintype "bidirectional"))
      (node (ref "IC4") (pin "3") (pinfunction "CE_3") (pintype "bidirectional"))
      (node (ref "Q1") (pin "2") (pinfunction "S_2") (pintype "bidirectional"))
    )
    (net (code "23") (name "Net-(D3-A)") (class "Default")
      (node (ref "C4") (pin "1") (pinfunction "1_1") (pintype "passive"))
      (node (ref "D3") (pin "2") (pinfunction "A_2") (pintype "bidirectional"))
      (node (ref "D4") (pin "1") (pinfunction "K_1") (pintype "bidirectional"))
    )
    (net (code "24") (name "Net-(D7-CATHODE)") (class "Default")
      (node (ref "D7") (pin "1") (pinfunction "CATHODE_1") (pintype "bidirectional"))
      (node (ref "R_CAPACITOR") (pin "2") (pinfunction "2_2") (pintype "passive"))
    )
    (net (code "25") (name "Net-(EPD_C1-Pad1)") (class "Default")
      (node (ref "EPD_C1") (pin "1") (pinfunction "1_1") (pintype "passive"))
      (node (ref "J1") (pin "4") (pinfunction "4_4") (pintype "bidirectional"))
    )
    (net (code "26") (name "Net-(EPD_C2-Pad1)") (class "Default")
      (node (ref "EPD_C2") (pin "1") (pinfunction "1_1") (pintype "passive"))
      (node (ref "J1") (pin "5") (pinfunction "5_5") (pintype "bidirectional"))
    )
    (net (code "27") (name "Net-(EPD_C6-Pad1)") (class "Default")
      (node (ref "EPD_C6") (pin "1") (pinfunction "1_1") (pintype "passive"))
      (node (ref "J1") (pin "18") (pinfunction "18_18") (pintype "bidirectional"))
    )
    (net (code "28") (name "Net-(EPD_C7-Pad1)") (class "Default")
      (node (ref "EPD_C7") (pin "1") (pinfunction "1_1") (pintype "passive"))
      (node (ref "J1") (pin "19") (pinfunction "19_19") (pintype "bidirectional"))
    )
    (net (code "29") (name "Net-(EPD_C8-Pad1)") (class "Default")
      (node (ref "EPD_C8") (pin "1") (pinfunction "1_1") (pintype "passive"))
      (node (ref "J1") (pin "20") (pinfunction "20_20") (pintype "bidirectional"))
    )
    (net (code "30") (name "Net-(EPD_C10-Pad1)") (class "Default")
      (node (ref "EPD_C10") (pin "1") (pinfunction "1_1") (pintype "passive"))
      (node (ref "J1") (pin "22") (pinfunction "22_22") (pintype "bidirectional"))
    )
    (net (code "31") (name "Net-(EPD_C12-Pad1)") (class "Default")
      (node (ref "EPD_C12") (pin "1") (pinfunction "1_1") (pintype "passive"))
      (node (ref "J1") (pin "24") (pinfunction "24_24") (pintype "bidirectional"))
    )
    (net (code "32") (name "Net-(IC1-CT)") (class "Default")
      (node (ref "C_DELAY") (pin "1") (pinfunction "1_1") (pintype "passive"))
      (node (ref "IC1") (pin "5") (pinfunction "CT_5") (pintype "bidirectional"))
    )
    (net (code "33") (name "Net-(J2-PadA5)") (class "Default")
      (node (ref "J2") (pin "A5") (pinfunction "A5_A5") (pintype "bidirectional"))
      (node (ref "R2-USB1") (pin "2") (pinfunction "2_2") (pintype "passive"))
    )
    (net (code "34") (name "Net-(J2-PadB5)") (class "Default")
      (node (ref "J2") (pin "B5") (pinfunction "B5_B5") (pintype "bidirectional"))
      (node (ref "R2-USB") (pin "1") (pinfunction "1_1") (pintype "passive"))
    )
    (net (code "35") (name "Net-(MCP73831-PROG)") (class "Default")
      (node (ref "MCP73831") (pin "5") (pinfunction "PROG_5") (pintype "input"))
      (node (ref "R2_BAT") (pin "2") (pinfunction "2_2") (pintype "passive"))
    )
    (net (code "36") (name "Net-(MCP73831-STAT)") (class "Default")
      (node (ref "MCP73831") (pin "1") (pinfunction "STAT_1") (pintype "output"))
      (node (ref "R1_BAT") (pin "1") (pinfunction "1_1") (pintype "passive"))
    )
    (net (code "37") (name "PREVGH") (class "Default")
      (node (ref "D5") (pin "1") (pinfunction "K_1") (pintype "bidirectional"))
      (node (ref "EPD_C9") (pin "1") (pinfunction "1_1") (pintype "passive"))
      (node (ref "J1") (pin "21") (pinfunction "21_21") (pintype "bidirectional"))
    )
    (net (code "38") (name "PREVGL") (class "Default")
      (node (ref "D4") (pin "2") (pinfunction "A_2") (pintype "bidirectional"))
      (node (ref "EPD_C11") (pin "1") (pinfunction "1_1") (pintype "passive"))
      (node (ref "J1") (pin "23") (pinfunction "23_23") (pintype "bidirectional"))
    )
    (net (code "39") (name "RESE") (class "Default")
      (node (ref "J1") (pin "3") (pinfunction "3_3") (pintype "bidirectional"))
      (node (ref "Q3") (pin "2") (pinfunction "S_2") (pintype "bidirectional"))
      (node (ref "R3") (pin "1") (pinfunction "1_1") (pintype "passive"))
    )
    (net (code "40") (name "RESE'") (class "Default")
      (node (ref "R2") (pin "2") (pinfunction "2_2") (pintype "passive"))
      (node (ref "R3") (pin "2") (pinfunction "2_2") (pintype "passive"))
      (node (ref "SJ1") (pin "2") (pinfunction "2_2") (pintype "passive"))
    )
    (net (code "41") (name "RESET") (class "Default")
      (node (ref "C5") (pin "1") (pinfunction "1_1") (pintype "passive"))
      (node (ref "IC1") (pin "1") (pinfunction "VOUT_1") (pintype "bidirectional"))
      (node (ref "RESET_BUTTON") (pin "3") (pinfunction "3_3") (pintype "passive"))
      (node (ref "RESET_BUTTON") (pin "4") (pinfunction "4_4") (pintype "passive"))
      (node (ref "R_RESET") (pin "2") (pinfunction "2_2") (pintype "passive"))
      (node (ref "U2") (pin "3") (pinfunction "EN_3") (pintype "input"))
    )
    (net (code "42") (name "RTC_RST") (class "Default")
      (node (ref "U2") (pin "16") (pinfunction "IO18_16") (pintype "bidirectional"))
      (node (ref "U3") (pin "4") (pinfunction "~{RST}_4") (pintype "input"))
    )
    (net (code "43") (name "RX") (class "Default")
      (node (ref "TP2") (pin "TP") (pinfunction "TP_TP") (pintype "input"))
      (node (ref "U2") (pin "24") (pinfunction "RXD0/GPIO17_24") (pintype "bidirectional"))
    )
    (net (code "44") (name "SCK") (class "Default")
      (node (ref "D10") (pin "2") (pinfunction "2_2") (pintype "passive"))
      (node (ref "J1") (pin "13") (pinfunction "13_13") (pintype "bidirectional"))
      (node (ref "J4") (pin "P5") (pinfunction "CLK_P5") (pintype "bidirectional"))
      (node (ref "R6") (pin "1") (pinfunction "1_1") (pintype "passive"))
      (node (ref "TP8") (pin "TP") (pinfunction "TP_TP") (pintype "input"))
      (node (ref "U1") (pin "6") (pinfunction "CLK_6") (pintype "input"))
      (node (ref "U2") (pin "6") (pinfunction "IO6_6") (pintype "bidirectional"))
    )
    (net (code "45") (name "SCL") (class "Default")
      (node (ref "J3") (pin "4") (pinfunction "4_4") (pintype "passive"))
      (node (ref "R2-PINH") (pin "1") (pinfunction "1_1") (pintype "passive"))
      (node (ref "SENSOR2") (pin "4") (pinfunction "SCK_4") (pintype "input"))
      (node (ref "U2") (pin "20") (pinfunction "IO22_20") (pintype "bidirectional"))
      (node (ref "U3") (pin "16") (pinfunction "SCL_16") (pintype "input"))
      (node (ref "U4") (pin "7") (pinfunction "SCL_7") (pintype "input"))
    )
    (net (code "46") (name "SDA") (class "Default")
      (node (ref "J3") (pin "3") (pinfunction "3_3") (pintype "passive"))
      (node (ref "R1_PINH") (pin "1") (pinfunction "1_1") (pintype "passive"))
      (node (ref "SENSOR2") (pin "3") (pinfunction "SDI_3") (pintype "bidirectional"))
      (node (ref "U2") (pin "19") (pinfunction "IO21_19") (pintype "bidirectional"))
      (node (ref "U3") (pin "15") (pinfunction "SDA_15") (pintype "bidirectional"))
      (node (ref "U4") (pin "8") (pinfunction "SDA_8") (pintype "bidirectional"))
    )
    (net (code "47") (name "SRC") (class "Default")
      (node (ref "C4") (pin "2") (pinfunction "2_2") (pintype "passive"))
      (node (ref "D5") (pin "2") (pinfunction "A_2") (pintype "bidirectional"))
      (node (ref "L1") (pin "1") (pinfunction "1_1") (pintype "passive"))
      (node (ref "Q3") (pin "3") (pinfunction "D_3") (pintype "bidirectional"))
    )
    (net (code "48") (name "SS_SD") (class "Default")
      (node (ref "D8") (pin "2") (pinfunction "2_2") (pintype "passive"))
      (node (ref "J4") (pin "P2") (pinfunction "CD/DAT3_P2") (pintype "bidirectional"))
      (node (ref "R10") (pin "1") (pinfunction "1_1") (pintype "passive"))
      (node (ref "U2") (pin "4") (pinfunction "IO4_4") (pintype "bidirectional"))
    )
    (net (code "49") (name "TX") (class "Default")
      (node (ref "TP1") (pin "TP") (pinfunction "TP_TP") (pintype "input"))
      (node (ref "U2") (pin "25") (pinfunction "TXD0/GPIO16_25") (pintype "bidirectional"))
    )
    (net (code "50") (name "USB_D+") (class "Default")
      (node (ref "D1") (pin "1") (pinfunction "I/O1_1_1") (pintype "bidirectional"))
      (node (ref "U2") (pin "14") (pinfunction "IO13_14") (pintype "bidirectional"))
    )
    (net (code "51") (name "USB_D-") (class "Default")
      (node (ref "D1") (pin "3") (pinfunction "I/O2_1_3") (pintype "bidirectional"))
      (node (ref "U2") (pin "13") (pinfunction "IO12_13") (pintype "bidirectional"))
    )
    (net (code "52") (name "VBAT") (class "Default")
      (node (ref "C2_BAT") (pin "1") (pinfunction "1_1") (pintype "passive"))
      (node (ref "MCP73831") (pin "3") (pinfunction "VBAT_3") (pintype "power_in"))
      (node (ref "Q1") (pin "3") (pinfunction "D_3") (pintype "bidirectional"))
      (node (ref "TP3") (pin "TP") (pinfunction "TP_TP") (pintype "input"))
      (node (ref "U4") (pin "2") (pinfunction "CELL_2") (pintype "power_in"))
      (node (ref "U4") (pin "3") (pinfunction "VDD_3") (pintype "power_in"))
    )
    (net (code "53") (name "VBUS") (class "Default")
      (node (ref "C1_BAT") (pin "1") (pinfunction "1_1") (pintype "passive"))
      (node (ref "C4_USB") (pin "1") (pinfunction "1_1") (pintype "passive"))
      (node (ref "C5_USB") (pin "1") (pinfunction "1_1") (pintype "passive"))
      (node (ref "CHG_LED") (pin "A") (pinfunction "A_A") (pintype "passive"))
      (node (ref "D1") (pin "5") (pinfunction "VBUS_5") (pintype "bidirectional"))
      (node (ref "D2") (pin "2") (pinfunction "ANODE_2") (pintype "bidirectional"))
      (node (ref "MCP73831") (pin "4") (pinfunction "VIN_4") (pintype "power_in"))
      (node (ref "PFMF.050.1") (pin "2") (pinfunction "2_2") (pintype "passive"))
      (node (ref "Q1") (pin "1") (pinfunction "G_1") (pintype "bidirectional"))
      (node (ref "R1_PWRUSB") (pin "2") (pinfunction "2_2") (pintype "passive"))
      (node (ref "TP14") (pin "TP") (pinfunction "TP_TP") (pintype "input"))
    )
    (net (code "54") (name "VRTC") (class "Default")
      (node (ref "C10_SUPERCAP") (pin "2") (pinfunction "2_2") (pintype "passive"))
      (node (ref "C8") (pin "1") (pinfunction "1_1") (pintype "passive"))
      (node (ref "R_CAPACITOR") (pin "1") (pinfunction "1_1") (pintype "passive"))
      (node (ref "U3") (pin "14") (pinfunction "VBAT_14") (pintype "power_in"))
    )
    (net (code "55") (name "VUSB") (class "Default")
      (node (ref "J2") (pin "A4") (pinfunction "A4_A4") (pintype "bidirectional"))
      (node (ref "J2") (pin "A9") (pinfunction "A9_A9") (pintype "bidirectional"))
      (node (ref "J2") (pin "B4") (pinfunction "B4_B4") (pintype "bidirectional"))
      (node (ref "J2") (pin "B9") (pinfunction "B9_B9") (pintype "bidirectional"))
      (node (ref "PFMF.050.1") (pin "1") (pinfunction "1_1") (pintype "passive"))
    )
    (net (code "56") (name "unconnected-(IC1-NC-Pad4)") (class "Default")
      (node (ref "IC1") (pin "4") (pinfunction "NC_4") (pintype "no_connect"))
    )
    (net (code "57") (name "unconnected-(IC4-NC-Pad4)") (class "Default")
      (node (ref "IC4") (pin "4") (pinfunction "NC_4") (pintype "no_connect"))
    )
    (net (code "58") (name "unconnected-(J1-Pad1)") (class "Default")
      (node (ref "J1") (pin "1") (pinfunction "1_1") (pintype "bidirectional"))
    )
    (net (code "59") (name "unconnected-(J1-Pad6)") (class "Default")
      (node (ref "J1") (pin "6") (pinfunction "6_6") (pintype "bidirectional"))
    )
    (net (code "60") (name "unconnected-(J1-Pad7)") (class "Default")
      (node (ref "J1") (pin "7") (pinfunction "7_7") (pintype "bidirectional"))
    )
    (net (code "61") (name "unconnected-(J2-PadA8)") (class "Default")
      (node (ref "J2") (pin "A8") (pinfunction "A8_A8") (pintype "bidirectional"))
    )
    (net (code "62") (name "unconnected-(J2-PadB8)") (class "Default")
      (node (ref "J2") (pin "B8") (pinfunction "B8_B8") (pintype "bidirectional"))
    )
    (net (code "63") (name "unconnected-(J4-DAT1-PadP8)") (class "Default")
      (node (ref "J4") (pin "P8") (pinfunction "DAT1_P8") (pintype "bidirectional"))
    )
    (net (code "64") (name "unconnected-(J4-DAT2-PadP1)") (class "Default")
      (node (ref "J4") (pin "P1") (pinfunction "DAT2_P1") (pintype "bidirectional"))
    )
    (net (code "65") (name "unconnected-(J4-DETECTION_1-PadS1)") (class "Default")
      (node (ref "J4") (pin "S1") (pinfunction "DETECTION_1_S1") (pintype "bidirectional"))
    )
    (net (code "66") (name "unconnected-(J4-DETECTION_2-PadS2)") (class "Default")
      (node (ref "J4") (pin "S2") (pinfunction "DETECTION_2_S2") (pintype "bidirectional"))
    )
    (net (code "67") (name "unconnected-(U2-NC-Pad22)") (class "Default")
      (node (ref "U2") (pin "22") (pinfunction "NC_22") (pintype "no_connect"))
    )
    (net (code "68") (name "unconnected-(U4-~{ALERT}-Pad5)") (class "Default")
      (node (ref "U4") (pin "5") (pinfunction "~{ALERT}_5") (pintype "output"))
    )
  )
)
